# adsr2_v2.net
KiCad netlist of a schematic drawn in EAGLE
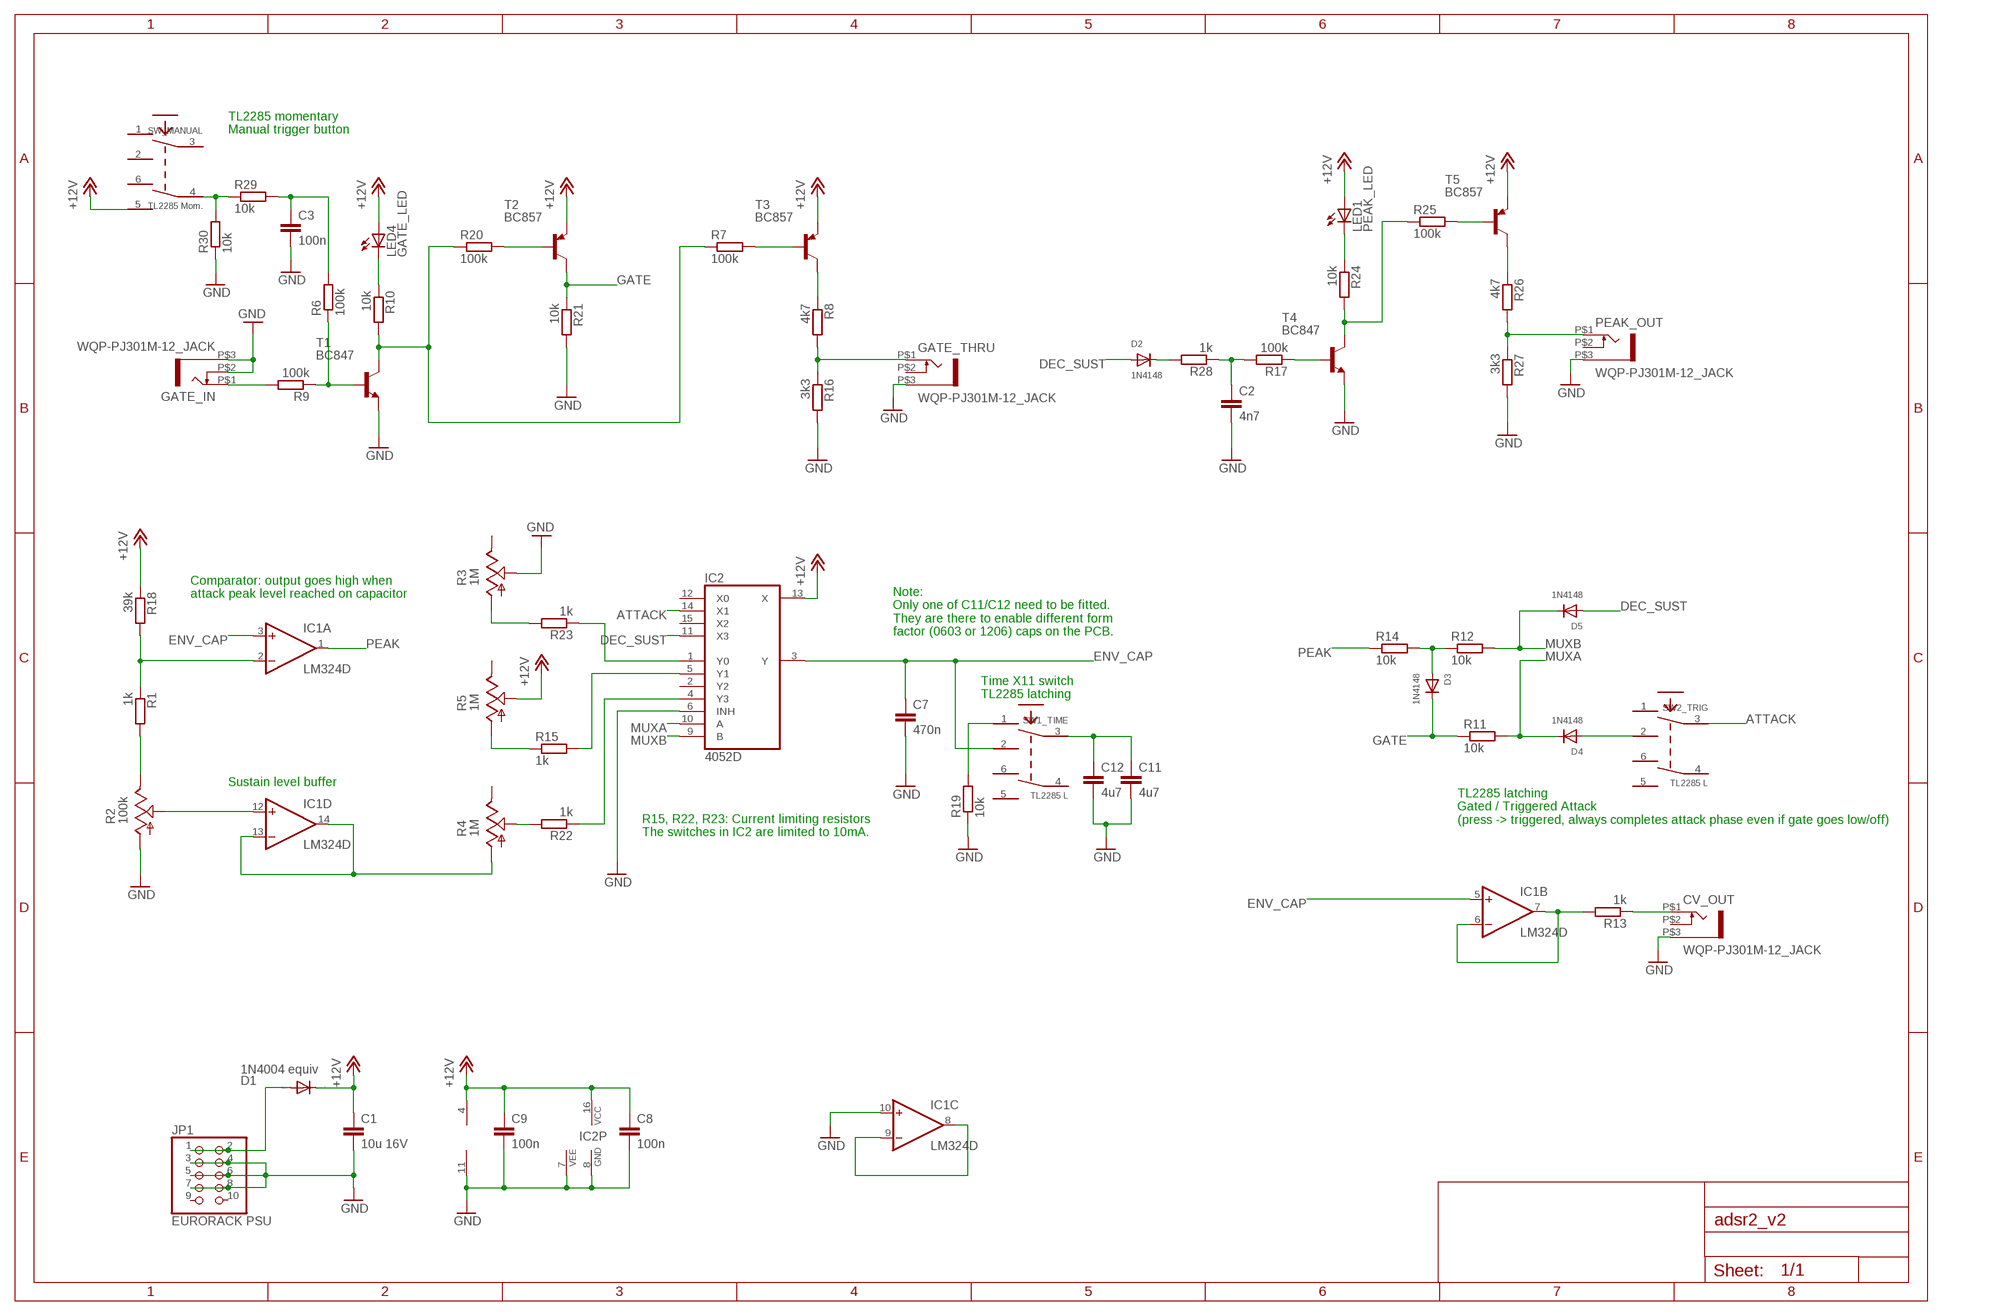
[diagram p0: schematic, sheet 1]

(export (version "E")
  (design (tool "Eeschema 10.0.6"))
  (components
    (comp (ref "C1")
      (value "10u 16V")
      (footprint "eagle-import:C1206K")
      (libsource (lib "eagle-import") (part "C-EUC1206K"))
    )
    (comp (ref "C2")
      (value "4n7")
      (footprint "eagle-import:C0603K")
      (libsource (lib "eagle-import") (part "C-EUC0603K"))
    )
    (comp (ref "C3")
      (value "100n")
      (footprint "eagle-import:C0603K")
      (libsource (lib "eagle-import") (part "C-EUC0603K"))
    )
    (comp (ref "C7")
      (value "470n")
      (footprint "eagle-import:C0603K")
      (libsource (lib "eagle-import") (part "C-EUC0603K"))
    )
    (comp (ref "C8")
      (value "100n")
      (footprint "eagle-import:C0603K")
      (libsource (lib "eagle-import") (part "C-EUC0603K"))
    )
    (comp (ref "C9")
      (value "100n")
      (footprint "eagle-import:C0603K")
      (libsource (lib "eagle-import") (part "C-EUC0603K"))
    )
    (comp (ref "C11")
      (value "4u7")
      (footprint "eagle-import:C1206K")
      (libsource (lib "eagle-import") (part "C-EUC1206K"))
    )
    (comp (ref "C12")
      (value "4u7")
      (footprint "eagle-import:C0603K")
      (libsource (lib "eagle-import") (part "C-EUC0603K"))
    )
    (comp (ref "CV_OUT")
      (value "WQP-PJ301M-12_JACK")
      (footprint "eagle-import:WQP-PJ301M-12_JACK")
      (libsource (lib "eagle-import") (part "WQP-PJ301M-12_JACK"))
    )
    (comp (ref "D1")
      (value "1N4004 equiv")
      (footprint "eagle-import:DO214AA")
      (libsource (lib "eagle-import") (part "DIODE-DO214AA"))
    )
    (comp (ref "D2")
      (value "1N4148")
      (footprint "eagle-import:SOD-323F")
      (libsource (lib "eagle-import") (part "DIODESOD-323F"))
    )
    (comp (ref "D3")
      (value "1N4148")
      (footprint "eagle-import:SOD-323F")
      (libsource (lib "eagle-import") (part "DIODESOD-323F"))
    )
    (comp (ref "D4")
      (value "1N4148")
      (footprint "eagle-import:SOD-323F")
      (libsource (lib "eagle-import") (part "DIODESOD-323F"))
    )
    (comp (ref "D5")
      (value "1N4148")
      (footprint "eagle-import:SOD-323F")
      (libsource (lib "eagle-import") (part "DIODESOD-323F"))
    )
    (comp (ref "GATE_IN")
      (value "WQP-PJ301M-12_JACK")
      (footprint "eagle-import:WQP-PJ301M-12_JACK")
      (libsource (lib "eagle-import") (part "WQP-PJ301M-12_JACK"))
    )
    (comp (ref "GATE_THRU")
      (value "WQP-PJ301M-12_JACK")
      (footprint "eagle-import:WQP-PJ301M-12_JACK")
      (libsource (lib "eagle-import") (part "WQP-PJ301M-12_JACK"))
    )
    (comp (ref "IC1")
      (value "LM324D")
      (footprint "eagle-import:SO14")
      (libsource (lib "eagle-import") (part "LM324D"))
    )
    (comp (ref "IC2")
      (value "4052D")
      (footprint "eagle-import:SO16")
      (libsource (lib "eagle-import") (part "4052D"))
    )
    (comp (ref "JP1")
      (value "EURORACK PSU")
      (footprint "eagle-import:2X05")
      (libsource (lib "eagle-import") (part "PINHD-2X5"))
    )
    (comp (ref "LED1")
      (value "PEAK_LED")
      (footprint "eagle-import:LED5MM")
      (libsource (lib "eagle-import") (part "LED5MM"))
    )
    (comp (ref "LED4")
      (value "GATE_LED")
      (footprint "eagle-import:LED5MM")
      (libsource (lib "eagle-import") (part "LED5MM"))
    )
    (comp (ref "PEAK_OUT")
      (value "WQP-PJ301M-12_JACK")
      (footprint "eagle-import:WQP-PJ301M-12_JACK")
      (libsource (lib "eagle-import") (part "WQP-PJ301M-12_JACK"))
    )
    (comp (ref "R1")
      (value "1k")
      (footprint "eagle-import:R0603")
      (libsource (lib "eagle-import") (part "R-EU_R0603"))
    )
    (comp (ref "R2")
      (value "100k")
      (footprint "eagle-import:ALPS_POT_VERTICAL")
      (libsource (lib "eagle-import") (part "POT_USVERTICAL"))
    )
    (comp (ref "R3")
      (value "1M")
      (footprint "eagle-import:ALPS_POT_VERTICAL")
      (libsource (lib "eagle-import") (part "POT_USVERTICAL"))
    )
    (comp (ref "R4")
      (value "1M")
      (footprint "eagle-import:ALPS_POT_VERTICAL")
      (libsource (lib "eagle-import") (part "POT_USVERTICAL"))
    )
    (comp (ref "R5")
      (value "1M")
      (footprint "eagle-import:ALPS_POT_VERTICAL")
      (libsource (lib "eagle-import") (part "POT_USVERTICAL"))
    )
    (comp (ref "R6")
      (value "100k")
      (footprint "eagle-import:R0603")
      (libsource (lib "eagle-import") (part "R-EU_R0603"))
    )
    (comp (ref "R7")
      (value "100k")
      (footprint "eagle-import:R0603")
      (libsource (lib "eagle-import") (part "R-EU_R0603"))
    )
    (comp (ref "R8")
      (value "4k7")
      (footprint "eagle-import:R0603")
      (libsource (lib "eagle-import") (part "R-EU_R0603"))
    )
    (comp (ref "R9")
      (value "100k")
      (footprint "eagle-import:R0603")
      (libsource (lib "eagle-import") (part "R-EU_R0603"))
    )
    (comp (ref "R10")
      (value "10k")
      (footprint "eagle-import:R0603")
      (libsource (lib "eagle-import") (part "R-EU_R0603"))
    )
    (comp (ref "R11")
      (value "10k")
      (footprint "eagle-import:R0603")
      (libsource (lib "eagle-import") (part "R-EU_R0603"))
    )
    (comp (ref "R12")
      (value "10k")
      (footprint "eagle-import:R0603")
      (libsource (lib "eagle-import") (part "R-EU_R0603"))
    )
    (comp (ref "R13")
      (value "1k")
      (footprint "eagle-import:R0603")
      (libsource (lib "eagle-import") (part "R-EU_R0603"))
    )
    (comp (ref "R14")
      (value "10k")
      (footprint "eagle-import:R0603")
      (libsource (lib "eagle-import") (part "R-EU_R0603"))
    )
    (comp (ref "R15")
      (value "1k")
      (footprint "eagle-import:R0603")
      (libsource (lib "eagle-import") (part "R-EU_R0603"))
    )
    (comp (ref "R16")
      (value "3k3")
      (footprint "eagle-import:R0603")
      (libsource (lib "eagle-import") (part "R-EU_R0603"))
    )
    (comp (ref "R17")
      (value "100k")
      (footprint "eagle-import:R0603")
      (libsource (lib "eagle-import") (part "R-EU_R0603"))
    )
    (comp (ref "R18")
      (value "39k")
      (footprint "eagle-import:R0603")
      (libsource (lib "eagle-import") (part "R-EU_R0603"))
    )
    (comp (ref "R19")
      (value "10k")
      (footprint "eagle-import:R0603")
      (libsource (lib "eagle-import") (part "R-EU_R0603"))
    )
    (comp (ref "R20")
      (value "100k")
      (footprint "eagle-import:R0603")
      (libsource (lib "eagle-import") (part "R-EU_R0603"))
    )
    (comp (ref "R21")
      (value "10k")
      (footprint "eagle-import:R0603")
      (libsource (lib "eagle-import") (part "R-EU_R0603"))
    )
    (comp (ref "R22")
      (value "1k")
      (footprint "eagle-import:R0603")
      (libsource (lib "eagle-import") (part "R-EU_R0603"))
    )
    (comp (ref "R23")
      (value "1k")
      (footprint "eagle-import:R0603")
      (libsource (lib "eagle-import") (part "R-EU_R0603"))
    )
    (comp (ref "R24")
      (value "10k")
      (footprint "eagle-import:R0603")
      (libsource (lib "eagle-import") (part "R-EU_R0603"))
    )
    (comp (ref "R25")
      (value "100k")
      (footprint "eagle-import:R0603")
      (libsource (lib "eagle-import") (part "R-EU_R0603"))
    )
    (comp (ref "R26")
      (value "4k7")
      (footprint "eagle-import:R0603")
      (libsource (lib "eagle-import") (part "R-EU_R0603"))
    )
    (comp (ref "R27")
      (value "3k3")
      (footprint "eagle-import:R0603")
      (libsource (lib "eagle-import") (part "R-EU_R0603"))
    )
    (comp (ref "R28")
      (value "1k")
      (footprint "eagle-import:R0603")
      (libsource (lib "eagle-import") (part "R-EU_R0603"))
    )
    (comp (ref "R29")
      (value "10k")
      (footprint "eagle-import:R0603")
      (libsource (lib "eagle-import") (part "R-EU_R0603"))
    )
    (comp (ref "R30")
      (value "10k")
      (footprint "eagle-import:R0603")
      (libsource (lib "eagle-import") (part "R-EU_R0603"))
    )
    (comp (ref "SW1_TIME")
      (value "TL2285 L")
      (footprint "eagle-import:TL2285_PCB")
      (libsource (lib "eagle-import") (part "TL2285"))
    )
    (comp (ref "SW2_TRIG")
      (value "TL2285 L")
      (footprint "eagle-import:TL2285_PCB")
      (libsource (lib "eagle-import") (part "TL2285"))
    )
    (comp (ref "SW_MANUAL")
      (value "TL2285 Mom.")
      (footprint "eagle-import:TL2285_PCB")
      (libsource (lib "eagle-import") (part "TL2285"))
    )
    (comp (ref "T1")
      (value "BC847")
      (footprint "eagle-import:SOT23")
      (libsource (lib "eagle-import") (part "BC847"))
    )
    (comp (ref "T2")
      (value "BC857")
      (footprint "eagle-import:SOT23-BEC")
      (libsource (lib "eagle-import") (part "-PNP-SOT23-BECBC857A"))
    )
    (comp (ref "T3")
      (value "BC857")
      (footprint "eagle-import:SOT23-BEC")
      (libsource (lib "eagle-import") (part "-PNP-SOT23-BECBC857A"))
    )
    (comp (ref "T4")
      (value "BC847")
      (footprint "eagle-import:SOT23")
      (libsource (lib "eagle-import") (part "BC847"))
    )
    (comp (ref "T5")
      (value "BC857")
      (footprint "eagle-import:SOT23-BEC")
      (libsource (lib "eagle-import") (part "-PNP-SOT23-BECBC857A"))
    )
  )
  (nets
    (net (code "1") (name "+12V") (class "Default")
      (node (ref "C1") (pin "1") (pinfunction "1_1") (pintype "passive"))
      (node (ref "C8") (pin "1") (pinfunction "1_1") (pintype "passive"))
      (node (ref "C9") (pin "1") (pinfunction "1_1") (pintype "passive"))
      (node (ref "D1") (pin "C") (pinfunction "C_C") (pintype "passive"))
      (node (ref "IC1") (pin "4") (pinfunction "V+_4") (pintype "power_in"))
      (node (ref "IC2") (pin "13") (pinfunction "X_13") (pintype "bidirectional"))
      (node (ref "IC2") (pin "16") (pinfunction "VCC_16") (pintype "power_in"))
      (node (ref "LED1") (pin "A") (pinfunction "A_A") (pintype "passive"))
      (node (ref "LED4") (pin "A") (pinfunction "A_A") (pintype "passive"))
      (node (ref "R18") (pin "1") (pinfunction "1_1") (pintype "passive"))
      (node (ref "R5") (pin "P$2") (pinfunction "S_P$2") (pintype "passive"))
      (node (ref "SW_MANUAL") (pin "5") (pinfunction "P5_5") (pintype "bidirectional"))
      (node (ref "T2") (pin "E") (pinfunction "E_E") (pintype "passive"))
      (node (ref "T3") (pin "E") (pinfunction "E_E") (pintype "passive"))
      (node (ref "T5") (pin "E") (pinfunction "E_E") (pintype "passive"))
    )
    (net (code "2") (name "/ATTACK") (class "Default")
      (node (ref "IC2") (pin "14") (pinfunction "X1_14") (pintype "bidirectional"))
      (node (ref "SW2_TRIG") (pin "3") (pinfunction "P3_3") (pintype "bidirectional"))
    )
    (net (code "3") (name "/DEC_SUST") (class "Default")
      (node (ref "D2") (pin "A") (pinfunction "A_A") (pintype "passive"))
      (node (ref "D5") (pin "A") (pinfunction "A_A") (pintype "passive"))
      (node (ref "IC2") (pin "11") (pinfunction "X3_11") (pintype "bidirectional"))
    )
    (net (code "4") (name "/ENV_CAP") (class "Default")
      (node (ref "C7") (pin "1") (pinfunction "1_1") (pintype "passive"))
      (node (ref "IC1") (pin "3") (pinfunction "+IN_3") (pintype "input"))
      (node (ref "IC1") (pin "5") (pinfunction "+IN_5") (pintype "input"))
      (node (ref "IC2") (pin "3") (pinfunction "Y_3") (pintype "bidirectional"))
      (node (ref "SW1_TIME") (pin "2") (pinfunction "P2_2") (pintype "bidirectional"))
    )
    (net (code "5") (name "/GATE") (class "Default")
      (node (ref "D3") (pin "C") (pinfunction "C_C") (pintype "passive"))
      (node (ref "R11") (pin "1") (pinfunction "1_1") (pintype "passive"))
      (node (ref "R21") (pin "1") (pinfunction "1_1") (pintype "passive"))
      (node (ref "T2") (pin "C") (pinfunction "C_C") (pintype "passive"))
    )
    (net (code "6") (name "/MUXA") (class "Default")
      (node (ref "D4") (pin "C") (pinfunction "C_C") (pintype "passive"))
      (node (ref "IC2") (pin "10") (pinfunction "A_10") (pintype "input"))
      (node (ref "R11") (pin "2") (pinfunction "2_2") (pintype "passive"))
    )
    (net (code "7") (name "/MUXB") (class "Default")
      (node (ref "D5") (pin "C") (pinfunction "C_C") (pintype "passive"))
      (node (ref "IC2") (pin "9") (pinfunction "B_9") (pintype "input"))
      (node (ref "R12") (pin "2") (pinfunction "2_2") (pintype "passive"))
    )
    (net (code "8") (name "/PEAK") (class "Default")
      (node (ref "IC1") (pin "1") (pinfunction "OUT_1") (pintype "output"))
      (node (ref "R14") (pin "1") (pinfunction "1_1") (pintype "passive"))
    )
    (net (code "9") (name "GND") (class "Default")
      (node (ref "C1") (pin "2") (pinfunction "2_2") (pintype "passive"))
      (node (ref "C11") (pin "2") (pinfunction "2_2") (pintype "passive"))
      (node (ref "C12") (pin "2") (pinfunction "2_2") (pintype "passive"))
      (node (ref "C2") (pin "2") (pinfunction "2_2") (pintype "passive"))
      (node (ref "C3") (pin "2") (pinfunction "2_2") (pintype "passive"))
      (node (ref "C7") (pin "2") (pinfunction "2_2") (pintype "passive"))
      (node (ref "C8") (pin "2") (pinfunction "2_2") (pintype "passive"))
      (node (ref "C9") (pin "2") (pinfunction "2_2") (pintype "passive"))
      (node (ref "CV_OUT") (pin "P$3") (pinfunction "1_P$3") (pintype "passive"))
      (node (ref "GATE_IN") (pin "P$2") (pinfunction "3_P$2") (pintype "passive"))
      (node (ref "GATE_IN") (pin "P$3") (pinfunction "1_P$3") (pintype "passive"))
      (node (ref "GATE_THRU") (pin "P$3") (pinfunction "1_P$3") (pintype "passive"))
      (node (ref "IC1") (pin "10") (pinfunction "+IN_10") (pintype "input"))
      (node (ref "IC1") (pin "11") (pinfunction "V-_11") (pintype "power_in"))
      (node (ref "IC2") (pin "6") (pinfunction "INH_6") (pintype "input"))
      (node (ref "IC2") (pin "7") (pinfunction "VEE_7") (pintype "power_in"))
      (node (ref "IC2") (pin "8") (pinfunction "GND_8") (pintype "power_in"))
      (node (ref "JP1") (pin "3") (pinfunction "3_3") (pintype "passive"))
      (node (ref "JP1") (pin "4") (pinfunction "4_4") (pintype "passive"))
      (node (ref "JP1") (pin "5") (pinfunction "5_5") (pintype "passive"))
      (node (ref "JP1") (pin "6") (pinfunction "6_6") (pintype "passive"))
      (node (ref "JP1") (pin "7") (pinfunction "7_7") (pintype "passive"))
      (node (ref "JP1") (pin "8") (pinfunction "8_8") (pintype "passive"))
      (node (ref "PEAK_OUT") (pin "P$3") (pinfunction "1_P$3") (pintype "passive"))
      (node (ref "R16") (pin "2") (pinfunction "2_2") (pintype "passive"))
      (node (ref "R19") (pin "1") (pinfunction "1_1") (pintype "passive"))
      (node (ref "R2") (pin "P$3") (pinfunction "A_P$3") (pintype "passive"))
      (node (ref "R21") (pin "2") (pinfunction "2_2") (pintype "passive"))
      (node (ref "R27") (pin "2") (pinfunction "2_2") (pintype "passive"))
      (node (ref "R3") (pin "P$2") (pinfunction "S_P$2") (pintype "passive"))
      (node (ref "R30") (pin "1") (pinfunction "1_1") (pintype "passive"))
      (node (ref "T1") (pin "2") (pinfunction "E_2") (pintype "passive"))
      (node (ref "T4") (pin "2") (pinfunction "E_2") (pintype "passive"))
    )
    (net (code "10") (name "Net-(C2-Pad1)") (class "Default")
      (node (ref "C2") (pin "1") (pinfunction "1_1") (pintype "passive"))
      (node (ref "R17") (pin "2") (pinfunction "2_2") (pintype "passive"))
      (node (ref "R28") (pin "1") (pinfunction "1_1") (pintype "passive"))
    )
    (net (code "11") (name "Net-(C3-Pad1)") (class "Default")
      (node (ref "C3") (pin "1") (pinfunction "1_1") (pintype "passive"))
      (node (ref "R29") (pin "2") (pinfunction "2_2") (pintype "passive"))
      (node (ref "R6") (pin "2") (pinfunction "2_2") (pintype "passive"))
    )
    (net (code "12") (name "Net-(CV_OUT-2)") (class "Default")
      (node (ref "CV_OUT") (pin "P$1") (pinfunction "2_P$1") (pintype "passive"))
      (node (ref "R13") (pin "1") (pinfunction "1_1") (pintype "passive"))
    )
    (net (code "13") (name "Net-(D1-PadA)") (class "Default")
      (node (ref "D1") (pin "A") (pinfunction "A_A") (pintype "passive"))
      (node (ref "JP1") (pin "1") (pinfunction "1_1") (pintype "passive"))
      (node (ref "JP1") (pin "2") (pinfunction "2_2") (pintype "passive"))
    )
    (net (code "14") (name "Net-(D2-PadC)") (class "Default")
      (node (ref "D2") (pin "C") (pinfunction "C_C") (pintype "passive"))
      (node (ref "R28") (pin "2") (pinfunction "2_2") (pintype "passive"))
    )
    (net (code "15") (name "Net-(D3-PadA)") (class "Default")
      (node (ref "D3") (pin "A") (pinfunction "A_A") (pintype "passive"))
      (node (ref "R12") (pin "1") (pinfunction "1_1") (pintype "passive"))
      (node (ref "R14") (pin "2") (pinfunction "2_2") (pintype "passive"))
    )
    (net (code "16") (name "Net-(GATE_IN-2)") (class "Default")
      (node (ref "GATE_IN") (pin "P$1") (pinfunction "2_P$1") (pintype "passive"))
      (node (ref "R9") (pin "2") (pinfunction "2_2") (pintype "passive"))
    )
    (net (code "17") (name "Net-(GATE_THRU-2)") (class "Default")
      (node (ref "GATE_THRU") (pin "P$1") (pinfunction "2_P$1") (pintype "passive"))
      (node (ref "R16") (pin "1") (pinfunction "1_1") (pintype "passive"))
      (node (ref "R8") (pin "2") (pinfunction "2_2") (pintype "passive"))
    )
    (net (code "18") (name "Net-(IC1A--IN)") (class "Default")
      (node (ref "IC1") (pin "2") (pinfunction "-IN_2") (pintype "input"))
      (node (ref "R1") (pin "1") (pinfunction "1_1") (pintype "passive"))
      (node (ref "R18") (pin "2") (pinfunction "2_2") (pintype "passive"))
    )
    (net (code "19") (name "Net-(IC1B--IN)") (class "Default")
      (node (ref "IC1") (pin "6") (pinfunction "-IN_6") (pintype "input"))
      (node (ref "IC1") (pin "7") (pinfunction "OUT_7") (pintype "output"))
      (node (ref "R13") (pin "2") (pinfunction "2_2") (pintype "passive"))
    )
    (net (code "20") (name "Net-(IC1C--IN)") (class "Default")
      (node (ref "IC1") (pin "8") (pinfunction "OUT_8") (pintype "output"))
      (node (ref "IC1") (pin "9") (pinfunction "-IN_9") (pintype "input"))
    )
    (net (code "21") (name "Net-(IC1D-+IN)") (class "Default")
      (node (ref "IC1") (pin "12") (pinfunction "+IN_12") (pintype "input"))
      (node (ref "R2") (pin "P$2") (pinfunction "S_P$2") (pintype "passive"))
    )
    (net (code "22") (name "Net-(IC1D--IN)") (class "Default")
      (node (ref "IC1") (pin "13") (pinfunction "-IN_13") (pintype "input"))
      (node (ref "IC1") (pin "14") (pinfunction "OUT_14") (pintype "output"))
      (node (ref "R4") (pin "P$3") (pinfunction "A_P$3") (pintype "passive"))
    )
    (net (code "23") (name "Net-(IC2A-Y0)") (class "Default")
      (node (ref "IC2") (pin "1") (pinfunction "Y0_1") (pintype "bidirectional"))
      (node (ref "R23") (pin "1") (pinfunction "1_1") (pintype "passive"))
    )
    (net (code "24") (name "Net-(IC2A-Y1)") (class "Default")
      (node (ref "IC2") (pin "5") (pinfunction "Y1_5") (pintype "bidirectional"))
      (node (ref "R15") (pin "2") (pinfunction "2_2") (pintype "passive"))
    )
    (net (code "25") (name "Net-(IC2A-Y3)") (class "Default")
      (node (ref "IC2") (pin "4") (pinfunction "Y3_4") (pintype "bidirectional"))
      (node (ref "R22") (pin "1") (pinfunction "1_1") (pintype "passive"))
    )
    (net (code "26") (name "Net-(LED1-C)") (class "Default")
      (node (ref "LED1") (pin "K") (pinfunction "C_K") (pintype "passive"))
      (node (ref "R24") (pin "1") (pinfunction "1_1") (pintype "passive"))
    )
    (net (code "27") (name "Net-(LED4-C)") (class "Default")
      (node (ref "LED4") (pin "K") (pinfunction "C_K") (pintype "passive"))
      (node (ref "R10") (pin "1") (pinfunction "1_1") (pintype "passive"))
    )
    (net (code "28") (name "Net-(PEAK_OUT-2)") (class "Default")
      (node (ref "PEAK_OUT") (pin "P$1") (pinfunction "2_P$1") (pintype "passive"))
      (node (ref "R26") (pin "2") (pinfunction "2_2") (pintype "passive"))
      (node (ref "R27") (pin "1") (pinfunction "1_1") (pintype "passive"))
    )
    (net (code "29") (name "Net-(R2-E)") (class "Default")
      (node (ref "R1") (pin "2") (pinfunction "2_2") (pintype "passive"))
      (node (ref "R2") (pin "P$1") (pinfunction "E_P$1") (pintype "passive"))
    )
    (net (code "30") (name "Net-(R3-A)") (class "Default")
      (node (ref "R23") (pin "2") (pinfunction "2_2") (pintype "passive"))
      (node (ref "R3") (pin "P$3") (pinfunction "A_P$3") (pintype "passive"))
    )
    (net (code "31") (name "Net-(R4-S)") (class "Default")
      (node (ref "R22") (pin "2") (pinfunction "2_2") (pintype "passive"))
      (node (ref "R4") (pin "P$2") (pinfunction "S_P$2") (pintype "passive"))
    )
    (net (code "32") (name "Net-(R5-A)") (class "Default")
      (node (ref "R15") (pin "1") (pinfunction "1_1") (pintype "passive"))
      (node (ref "R5") (pin "P$3") (pinfunction "A_P$3") (pintype "passive"))
    )
    (net (code "33") (name "Net-(R7-Pad2)") (class "Default")
      (node (ref "R7") (pin "2") (pinfunction "2_2") (pintype "passive"))
      (node (ref "T3") (pin "B") (pinfunction "B_B") (pintype "passive"))
    )
    (net (code "34") (name "Net-(R8-Pad1)") (class "Default")
      (node (ref "R8") (pin "1") (pinfunction "1_1") (pintype "passive"))
      (node (ref "T3") (pin "C") (pinfunction "C_C") (pintype "passive"))
    )
    (net (code "35") (name "Net-(R20-Pad2)") (class "Default")
      (node (ref "R20") (pin "2") (pinfunction "2_2") (pintype "passive"))
      (node (ref "T2") (pin "B") (pinfunction "B_B") (pintype "passive"))
    )
    (net (code "36") (name "Net-(R25-Pad2)") (class "Default")
      (node (ref "R25") (pin "2") (pinfunction "2_2") (pintype "passive"))
      (node (ref "T5") (pin "B") (pinfunction "B_B") (pintype "passive"))
    )
    (net (code "37") (name "Net-(R26-Pad1)") (class "Default")
      (node (ref "R26") (pin "1") (pinfunction "1_1") (pintype "passive"))
      (node (ref "T5") (pin "C") (pinfunction "C_C") (pintype "passive"))
    )
    (net (code "38") (name "Net-(SW1_TIME-P1)") (class "Default")
      (node (ref "R19") (pin "2") (pinfunction "2_2") (pintype "passive"))
      (node (ref "SW1_TIME") (pin "1") (pinfunction "P1_1") (pintype "bidirectional"))
    )
    (net (code "39") (name "Net-(SW1_TIME-P3)") (class "Default")
      (node (ref "C11") (pin "1") (pinfunction "1_1") (pintype "passive"))
      (node (ref "C12") (pin "1") (pinfunction "1_1") (pintype "passive"))
      (node (ref "SW1_TIME") (pin "3") (pinfunction "P3_3") (pintype "bidirectional"))
    )
    (net (code "40") (name "Net-(SW2_TRIG-P2)") (class "Default")
      (node (ref "D4") (pin "A") (pinfunction "A_A") (pintype "passive"))
      (node (ref "SW2_TRIG") (pin "2") (pinfunction "P2_2") (pintype "bidirectional"))
    )
    (net (code "41") (name "Net-(SW_MANUAL-P4)") (class "Default")
      (node (ref "R29") (pin "1") (pinfunction "1_1") (pintype "passive"))
      (node (ref "R30") (pin "2") (pinfunction "2_2") (pintype "passive"))
      (node (ref "SW_MANUAL") (pin "4") (pinfunction "P4_4") (pintype "bidirectional"))
    )
    (net (code "42") (name "Net-(T1-B)") (class "Default")
      (node (ref "R6") (pin "1") (pinfunction "1_1") (pintype "passive"))
      (node (ref "R9") (pin "1") (pinfunction "1_1") (pintype "passive"))
      (node (ref "T1") (pin "1") (pinfunction "B_1") (pintype "passive"))
    )
    (net (code "43") (name "Net-(T1-C)") (class "Default")
      (node (ref "R10") (pin "2") (pinfunction "2_2") (pintype "passive"))
      (node (ref "R20") (pin "1") (pinfunction "1_1") (pintype "passive"))
      (node (ref "R7") (pin "1") (pinfunction "1_1") (pintype "passive"))
      (node (ref "T1") (pin "3") (pinfunction "C_3") (pintype "passive"))
    )
    (net (code "44") (name "Net-(T4-B)") (class "Default")
      (node (ref "R17") (pin "1") (pinfunction "1_1") (pintype "passive"))
      (node (ref "T4") (pin "1") (pinfunction "B_1") (pintype "passive"))
    )
    (net (code "45") (name "Net-(T4-C)") (class "Default")
      (node (ref "R24") (pin "2") (pinfunction "2_2") (pintype "passive"))
      (node (ref "R25") (pin "1") (pinfunction "1_1") (pintype "passive"))
      (node (ref "T4") (pin "3") (pinfunction "C_3") (pintype "passive"))
    )
    (net (code "46") (name "unconnected-(CV_OUT-3-PadP$2)") (class "Default")
      (node (ref "CV_OUT") (pin "P$2") (pinfunction "3_P$2") (pintype "passive"))
    )
    (net (code "47") (name "unconnected-(GATE_THRU-3-PadP$2)") (class "Default")
      (node (ref "GATE_THRU") (pin "P$2") (pinfunction "3_P$2") (pintype "passive"))
    )
    (net (code "48") (name "unconnected-(IC2A-X0-Pad12)") (class "Default")
      (node (ref "IC2") (pin "12") (pinfunction "X0_12") (pintype "bidirectional"))
    )
    (net (code "49") (name "unconnected-(IC2A-X2-Pad15)") (class "Default")
      (node (ref "IC2") (pin "15") (pinfunction "X2_15") (pintype "bidirectional"))
    )
    (net (code "50") (name "unconnected-(IC2A-Y2-Pad2)") (class "Default")
      (node (ref "IC2") (pin "2") (pinfunction "Y2_2") (pintype "bidirectional"))
    )
    (net (code "51") (name "unconnected-(JP1-Pad9)") (class "Default")
      (node (ref "JP1") (pin "9") (pinfunction "9_9") (pintype "passive"))
    )
    (net (code "52") (name "unconnected-(JP1-Pad10)") (class "Default")
      (node (ref "JP1") (pin "10") (pinfunction "10_10") (pintype "passive"))
    )
    (net (code "53") (name "unconnected-(PEAK_OUT-3-PadP$2)") (class "Default")
      (node (ref "PEAK_OUT") (pin "P$2") (pinfunction "3_P$2") (pintype "passive"))
    )
    (net (code "54") (name "unconnected-(R3-E-PadP$1)") (class "Default")
      (node (ref "R3") (pin "P$1") (pinfunction "E_P$1") (pintype "passive"))
    )
    (net (code "55") (name "unconnected-(R4-E-PadP$1)") (class "Default")
      (node (ref "R4") (pin "P$1") (pinfunction "E_P$1") (pintype "passive"))
    )
    (net (code "56") (name "unconnected-(R5-E-PadP$1)") (class "Default")
      (node (ref "R5") (pin "P$1") (pinfunction "E_P$1") (pintype "passive"))
    )
    (net (code "57") (name "unconnected-(SW1_TIME-P4-Pad4)") (class "Default")
      (node (ref "SW1_TIME") (pin "4") (pinfunction "P4_4") (pintype "bidirectional"))
    )
    (net (code "58") (name "unconnected-(SW1_TIME-P5-Pad5)") (class "Default")
      (node (ref "SW1_TIME") (pin "5") (pinfunction "P5_5") (pintype "bidirectional"))
    )
    (net (code "59") (name "unconnected-(SW1_TIME-P6-Pad6)") (class "Default")
      (node (ref "SW1_TIME") (pin "6") (pinfunction "P6_6") (pintype "bidirectional"))
    )
    (net (code "60") (name "unconnected-(SW2_TRIG-P1-Pad1)") (class "Default")
      (node (ref "SW2_TRIG") (pin "1") (pinfunction "P1_1") (pintype "bidirectional"))
    )
    (net (code "61") (name "unconnected-(SW2_TRIG-P4-Pad4)") (class "Default")
      (node (ref "SW2_TRIG") (pin "4") (pinfunction "P4_4") (pintype "bidirectional"))
    )
    (net (code "62") (name "unconnected-(SW2_TRIG-P5-Pad5)") (class "Default")
      (node (ref "SW2_TRIG") (pin "5") (pinfunction "P5_5") (pintype "bidirectional"))
    )
    (net (code "63") (name "unconnected-(SW2_TRIG-P6-Pad6)") (class "Default")
      (node (ref "SW2_TRIG") (pin "6") (pinfunction "P6_6") (pintype "bidirectional"))
    )
    (net (code "64") (name "unconnected-(SW_MANUAL-P1-Pad1)") (class "Default")
      (node (ref "SW_MANUAL") (pin "1") (pinfunction "P1_1") (pintype "bidirectional"))
    )
    (net (code "65") (name "unconnected-(SW_MANUAL-P2-Pad2)") (class "Default")
      (node (ref "SW_MANUAL") (pin "2") (pinfunction "P2_2") (pintype "bidirectional"))
    )
    (net (code "66") (name "unconnected-(SW_MANUAL-P3-Pad3)") (class "Default")
      (node (ref "SW_MANUAL") (pin "3") (pinfunction "P3_3") (pintype "bidirectional"))
    )
    (net (code "67") (name "unconnected-(SW_MANUAL-P6-Pad6)") (class "Default")
      (node (ref "SW_MANUAL") (pin "6") (pinfunction "P6_6") (pintype "bidirectional"))
    )
  )
)
